# ESP32_A4_Landscape.net
KiCad netlist of a schematic drawn in Altium Designer
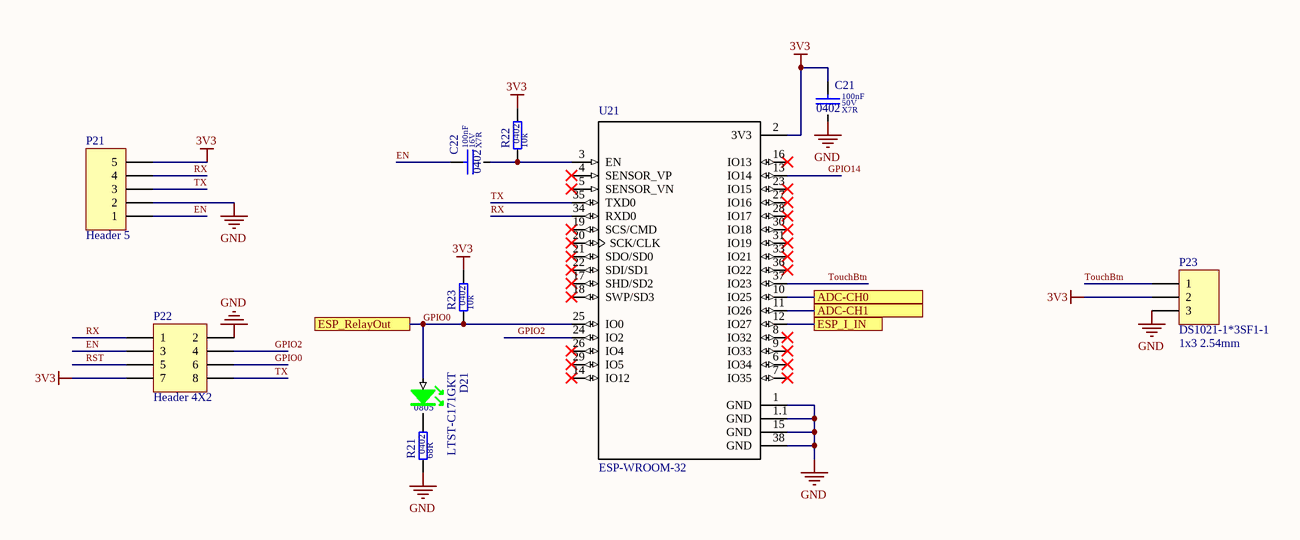
[diagram p0: ESP32_A4_Landscape.SchDoc]

(export (version "E")
  (design (tool "Eeschema 10.0.6"))
  (components
    (comp (ref "C21")
      (value "100nF")
      (footprint "C_0402_1005")
      (description "Capacitor")
      (fields
        (field (name "DIELECTRIC") "X7R")
        (field (name "VOLTAGE") "50V")
        (field (name "SCH_FOOTPRINT") "0402")
        (field (name "PART NUMBER") "C_100nF_50V_X7R_0402_10")
        (field (name "MANUFACTURER") "Murata")
      )
      (libsource (lib "Library") (part "C"))
    )
    (comp (ref "C22")
      (value "100nF")
      (footprint "C_0402_1005")
      (description "Capacitor")
      (fields
        (field (name "DIELECTRIC") "X7R")
        (field (name "VOLTAGE") "16V")
        (field (name "SCH_FOOTPRINT") "0402")
        (field (name "PART NUMBER") "C_100nF_16V_X7R_0402_10")
        (field (name "MANUFACTURER") "Murata")
      )
      (libsource (lib "Library") (part "C"))
    )
    (comp (ref "D21")
      (value "LTST-C171GKT")
      (footprint "OL_0805_2012")
      (description "LED GREEN")
      (fields
        (field (name "SCH_FOOTPRINT") "0805")
        (field (name "PART NUMBER") "OL_G_0805_0C006_LTST-C171GKT")
        (field (name "MANUFACTURER") "Lite-On")
      )
      (libsource (lib "Library") (part "OL_G"))
    )
    (comp (ref "P21")
      (value "Header 5")
      (footprint "HDR1X5")
      (description "Header, 5-Pin")
      (fields (field (name "PUBLISHER") "Altium Limited"))
      (libsource (lib "Miscellaneous Connectors") (part "Header 5"))
    )
    (comp (ref "P22")
      (value "Header 4X2")
      (footprint "HDR2X4")
      (description "Header, 4-Pin, Dual row")
      (fields (field (name "PUBLISHER") "Altium Limited"))
      (libsource (lib "Miscellaneous Connectors") (part "Header 4X2"))
    )
    (comp (ref "P23")
      (value "DS1021-1*3SF1-1")
      (footprint "P_HEADER_1x3_2.54")
      (description "Header, 3-Pin")
      (fields
        (field (name "PART NUMBER") "P_HEADER_1x3_2.54")
        (field (name "SCH_FOOTPRINT") "1x3 2.54mm")
        (field (name "MANUFACTURER") "Connfly")
      )
      (libsource (lib "Library") (part "P_HEADER_1x3"))
    )
    (comp (ref "R21")
      (value "68R")
      (footprint "R_0402_1005")
      (fields
        (field (name "SCH_FOOTPRINT") "0402")
        (field (name "PART NUMBER") "R_68R_0402")
        (field (name "VOLTAGE") "50V")
        (field (name "POWER") "63mW")
      )
      (libsource (lib "Library") (part "R"))
    )
    (comp (ref "R22")
      (value "10k")
      (footprint "R_0402_1005")
      (fields
        (field (name "SCH_FOOTPRINT") "0402")
        (field (name "PART NUMBER") "R_10k_0402_1")
        (field (name "VOLTAGE") "50V")
        (field (name "POWER") "63mW")
      )
      (libsource (lib "Library") (part "R"))
    )
    (comp (ref "R23")
      (value "10k")
      (footprint "R_0402_1005")
      (fields
        (field (name "SCH_FOOTPRINT") "0402")
        (field (name "PART NUMBER") "R_10k_0402_1")
        (field (name "VOLTAGE") "50V")
        (field (name "POWER") "63mW")
      )
      (libsource (lib "Library") (part "R"))
    )
    (comp (ref "U21")
      (value "ESP-WROOM-32")
      (footprint "*MODULE_ESP-WROOM-32_ESP-WROOM-32(Primary)")
      (description "Module: combo; GPIO, I2C x2, I2S x2, SDIO, SPI x3, UART x3; 19.5dBm")
      (fields (field (name "MF") "Olimex LTD"))
      (libsource (lib "ESP-WROOM-32") (part "ESP-WROOM-32"))
    )
  )
  (nets
    (net (code "1") (name "/ADC-CH0") (class "Default")
      (node (ref "U21") (pin "10") (pinfunction "IO25_10") (pintype "bidirectional"))
    )
    (net (code "2") (name "/ADC-CH1") (class "Default")
      (node (ref "U21") (pin "11") (pinfunction "IO26_11") (pintype "bidirectional"))
    )
    (net (code "3") (name "/EN") (class "Default")
      (node (ref "C22") (pin "1") (pinfunction "1_1") (pintype "passive"))
      (node (ref "P21") (pin "1") (pinfunction "1_1") (pintype "passive"))
      (node (ref "P22") (pin "3") (pinfunction "3_3") (pintype "passive"))
    )
    (net (code "4") (name "/ESP_I_IN") (class "Default")
      (node (ref "U21") (pin "12") (pinfunction "IO27_12") (pintype "bidirectional"))
    )
    (net (code "5") (name "/GPIO0") (class "Default")
      (node (ref "D21") (pin "2") (pinfunction "A_2") (pintype "input"))
      (node (ref "P22") (pin "6") (pinfunction "6_6") (pintype "passive"))
      (node (ref "R23") (pin "1") (pinfunction "1_1") (pintype "passive"))
      (node (ref "U21") (pin "25") (pinfunction "IO0_25") (pintype "bidirectional"))
    )
    (net (code "6") (name "/GPIO2") (class "Default")
      (node (ref "P22") (pin "4") (pinfunction "4_4") (pintype "passive"))
      (node (ref "U21") (pin "24") (pinfunction "IO2_24") (pintype "bidirectional"))
    )
    (net (code "7") (name "/GPIO14") (class "Default")
      (node (ref "U21") (pin "13") (pinfunction "IO14_13") (pintype "bidirectional"))
    )
    (net (code "8") (name "/RST") (class "Default")
      (node (ref "P22") (pin "5") (pinfunction "5_5") (pintype "passive"))
    )
    (net (code "9") (name "/RX") (class "Default")
      (node (ref "P21") (pin "4") (pinfunction "4_4") (pintype "passive"))
      (node (ref "P22") (pin "1") (pinfunction "1_1") (pintype "passive"))
      (node (ref "U21") (pin "34") (pinfunction "RXD0_34") (pintype "bidirectional"))
    )
    (net (code "10") (name "/TX") (class "Default")
      (node (ref "P21") (pin "3") (pinfunction "3_3") (pintype "passive"))
      (node (ref "P22") (pin "8") (pinfunction "8_8") (pintype "passive"))
      (node (ref "U21") (pin "35") (pinfunction "TXD0_35") (pintype "bidirectional"))
    )
    (net (code "11") (name "/TouchBtn") (class "Default")
      (node (ref "P23") (pin "1") (pinfunction "1_1") (pintype "passive"))
      (node (ref "U21") (pin "37") (pinfunction "IO23_37") (pintype "bidirectional"))
    )
    (net (code "12") (name "3V3") (class "Default")
      (node (ref "C21") (pin "1") (pinfunction "1_1") (pintype "passive"))
      (node (ref "P21") (pin "5") (pinfunction "5_5") (pintype "passive"))
      (node (ref "P22") (pin "7") (pinfunction "7_7") (pintype "passive"))
      (node (ref "P23") (pin "2") (pinfunction "2_2") (pintype "passive"))
      (node (ref "R22") (pin "2") (pinfunction "2_2") (pintype "passive"))
      (node (ref "R23") (pin "2") (pinfunction "2_2") (pintype "passive"))
      (node (ref "U21") (pin "2") (pinfunction "3V3_2") (pintype "power_in"))
    )
    (net (code "13") (name "GND") (class "Default")
      (node (ref "C21") (pin "2") (pinfunction "2_2") (pintype "passive"))
      (node (ref "P21") (pin "2") (pinfunction "2_2") (pintype "passive"))
      (node (ref "P22") (pin "2") (pinfunction "2_2") (pintype "passive"))
      (node (ref "P23") (pin "3") (pinfunction "3_3") (pintype "passive"))
      (node (ref "R21") (pin "1") (pinfunction "1_1") (pintype "passive"))
      (node (ref "U21") (pin "1") (pinfunction "GND_1") (pintype "power_in"))
      (node (ref "U21") (pin "1.1") (pinfunction "GND_1.1") (pintype "power_in"))
      (node (ref "U21") (pin "15") (pinfunction "GND_15") (pintype "power_in"))
      (node (ref "U21") (pin "38") (pinfunction "GND_38") (pintype "power_in"))
    )
    (net (code "14") (name "Net-(D21-K)") (class "Default")
      (node (ref "D21") (pin "1") (pinfunction "K_1") (pintype "output"))
      (node (ref "R21") (pin "2") (pinfunction "2_2") (pintype "passive"))
    )
    (net (code "15") (name "Net-(U21-EN)") (class "Default")
      (node (ref "C22") (pin "2") (pinfunction "2_2") (pintype "passive"))
      (node (ref "R22") (pin "1") (pinfunction "1_1") (pintype "passive"))
      (node (ref "U21") (pin "3") (pinfunction "EN_3") (pintype "input"))
    )
    (net (code "16") (name "unconnected-(U21-IO4-Pad26)") (class "Default")
      (node (ref "U21") (pin "26") (pinfunction "IO4_26") (pintype "bidirectional+no_connect"))
    )
    (net (code "17") (name "unconnected-(U21-IO5-Pad29)") (class "Default")
      (node (ref "U21") (pin "29") (pinfunction "IO5_29") (pintype "bidirectional+no_connect"))
    )
    (net (code "18") (name "unconnected-(U21-IO12-Pad14)") (class "Default")
      (node (ref "U21") (pin "14") (pinfunction "IO12_14") (pintype "bidirectional+no_connect"))
    )
    (net (code "19") (name "unconnected-(U21-IO13-Pad16)") (class "Default")
      (node (ref "U21") (pin "16") (pinfunction "IO13_16") (pintype "bidirectional+no_connect"))
    )
    (net (code "20") (name "unconnected-(U21-IO15-Pad23)") (class "Default")
      (node (ref "U21") (pin "23") (pinfunction "IO15_23") (pintype "bidirectional+no_connect"))
    )
    (net (code "21") (name "unconnected-(U21-IO16-Pad27)") (class "Default")
      (node (ref "U21") (pin "27") (pinfunction "IO16_27") (pintype "bidirectional+no_connect"))
    )
    (net (code "22") (name "unconnected-(U21-IO17-Pad28)") (class "Default")
      (node (ref "U21") (pin "28") (pinfunction "IO17_28") (pintype "bidirectional+no_connect"))
    )
    (net (code "23") (name "unconnected-(U21-IO18-Pad30)") (class "Default")
      (node (ref "U21") (pin "30") (pinfunction "IO18_30") (pintype "bidirectional+no_connect"))
    )
    (net (code "24") (name "unconnected-(U21-IO19-Pad31)") (class "Default")
      (node (ref "U21") (pin "31") (pinfunction "IO19_31") (pintype "bidirectional+no_connect"))
    )
    (net (code "25") (name "unconnected-(U21-IO21-Pad33)") (class "Default")
      (node (ref "U21") (pin "33") (pinfunction "IO21_33") (pintype "bidirectional+no_connect"))
    )
    (net (code "26") (name "unconnected-(U21-IO22-Pad36)") (class "Default")
      (node (ref "U21") (pin "36") (pinfunction "IO22_36") (pintype "bidirectional+no_connect"))
    )
    (net (code "27") (name "unconnected-(U21-IO32-Pad8)") (class "Default")
      (node (ref "U21") (pin "8") (pinfunction "IO32_8") (pintype "bidirectional+no_connect"))
    )
    (net (code "28") (name "unconnected-(U21-IO33-Pad9)") (class "Default")
      (node (ref "U21") (pin "9") (pinfunction "IO33_9") (pintype "bidirectional+no_connect"))
    )
    (net (code "29") (name "unconnected-(U21-IO34-Pad6)") (class "Default")
      (node (ref "U21") (pin "6") (pinfunction "IO34_6") (pintype "bidirectional+no_connect"))
    )
    (net (code "30") (name "unconnected-(U21-IO35-Pad7)") (class "Default")
      (node (ref "U21") (pin "7") (pinfunction "IO35_7") (pintype "bidirectional+no_connect"))
    )
    (net (code "31") (name "unconnected-(U21-SCK{slash}CLK-Pad20)") (class "Default")
      (node (ref "U21") (pin "20") (pinfunction "SCK/CLK_20") (pintype "bidirectional+no_connect"))
    )
    (net (code "32") (name "unconnected-(U21-SCS{slash}CMD-Pad19)") (class "Default")
      (node (ref "U21") (pin "19") (pinfunction "SCS/CMD_19") (pintype "bidirectional+no_connect"))
    )
    (net (code "33") (name "unconnected-(U21-SDI{slash}SD1-Pad22)") (class "Default")
      (node (ref "U21") (pin "22") (pinfunction "SDI/SD1_22") (pintype "bidirectional+no_connect"))
    )
    (net (code "34") (name "unconnected-(U21-SDO{slash}SD0-Pad21)") (class "Default")
      (node (ref "U21") (pin "21") (pinfunction "SDO/SD0_21") (pintype "bidirectional+no_connect"))
    )
    (net (code "35") (name "unconnected-(U21-SENSOR_VN-Pad5)") (class "Default")
      (node (ref "U21") (pin "5") (pinfunction "SENSOR_VN_5") (pintype "input+no_connect"))
    )
    (net (code "36") (name "unconnected-(U21-SENSOR_VP-Pad4)") (class "Default")
      (node (ref "U21") (pin "4") (pinfunction "SENSOR_VP_4") (pintype "input+no_connect"))
    )
    (net (code "37") (name "unconnected-(U21-SHD{slash}SD2-Pad17)") (class "Default")
      (node (ref "U21") (pin "17") (pinfunction "SHD/SD2_17") (pintype "bidirectional+no_connect"))
    )
    (net (code "38") (name "unconnected-(U21-SWP{slash}SD3-Pad18)") (class "Default")
      (node (ref "U21") (pin "18") (pinfunction "SWP/SD3_18") (pintype "bidirectional+no_connect"))
    )
  )
)
